# Left.net
KiCad netlist of a schematic drawn in EAGLE
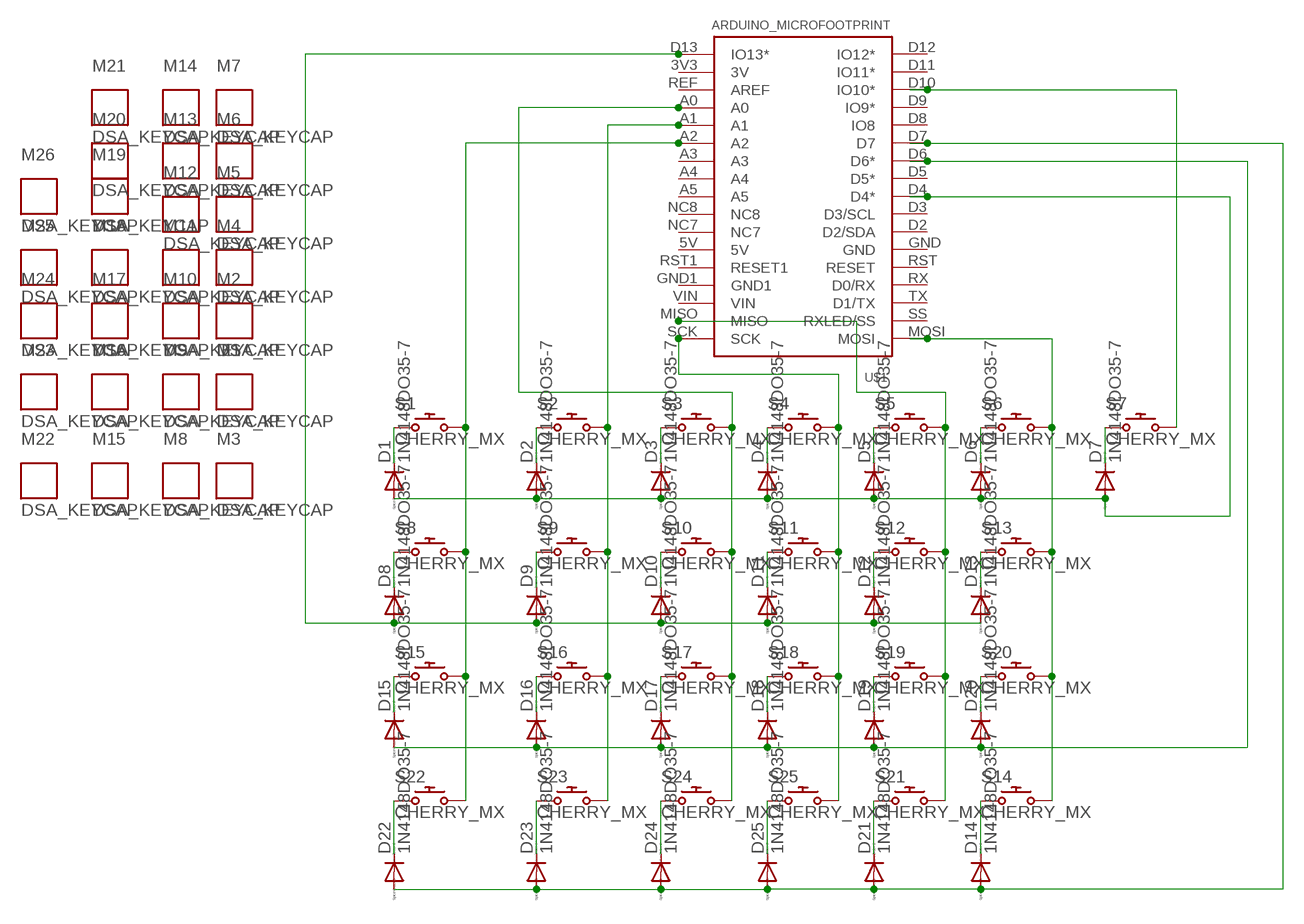
[diagram p0: schematic, sheet 1]

(export (version "E")
  (design (tool "Eeschema 10.0.6"))
  (components
    (comp (ref "D1")
      (value "1N4148DO35-7")
      (footprint "eagle-import:DO35-7")
      (libsource (lib "eagle-import") (part "1N4148DO35-7"))
    )
    (comp (ref "D2")
      (value "1N4148DO35-7")
      (footprint "eagle-import:DO35-7")
      (libsource (lib "eagle-import") (part "1N4148DO35-7"))
    )
    (comp (ref "D3")
      (value "1N4148DO35-7")
      (footprint "eagle-import:DO35-7")
      (libsource (lib "eagle-import") (part "1N4148DO35-7"))
    )
    (comp (ref "D4")
      (value "1N4148DO35-7")
      (footprint "eagle-import:DO35-7")
      (libsource (lib "eagle-import") (part "1N4148DO35-7"))
    )
    (comp (ref "D5")
      (value "1N4148DO35-7")
      (footprint "eagle-import:DO35-7")
      (libsource (lib "eagle-import") (part "1N4148DO35-7"))
    )
    (comp (ref "D6")
      (value "1N4148DO35-7")
      (footprint "eagle-import:DO35-7")
      (libsource (lib "eagle-import") (part "1N4148DO35-7"))
    )
    (comp (ref "D7")
      (value "1N4148DO35-7")
      (footprint "eagle-import:DO35-7")
      (libsource (lib "eagle-import") (part "1N4148DO35-7"))
    )
    (comp (ref "D8")
      (value "1N4148DO35-7")
      (footprint "eagle-import:DO35-7")
      (libsource (lib "eagle-import") (part "1N4148DO35-7"))
    )
    (comp (ref "D9")
      (value "1N4148DO35-7")
      (footprint "eagle-import:DO35-7")
      (libsource (lib "eagle-import") (part "1N4148DO35-7"))
    )
    (comp (ref "D10")
      (value "1N4148DO35-7")
      (footprint "eagle-import:DO35-7")
      (libsource (lib "eagle-import") (part "1N4148DO35-7"))
    )
    (comp (ref "D11")
      (value "1N4148DO35-7")
      (footprint "eagle-import:DO35-7")
      (libsource (lib "eagle-import") (part "1N4148DO35-7"))
    )
    (comp (ref "D12")
      (value "1N4148DO35-7")
      (footprint "eagle-import:DO35-7")
      (libsource (lib "eagle-import") (part "1N4148DO35-7"))
    )
    (comp (ref "D13")
      (value "1N4148DO35-7")
      (footprint "eagle-import:DO35-7")
      (libsource (lib "eagle-import") (part "1N4148DO35-7"))
    )
    (comp (ref "D14")
      (value "1N4148DO35-7")
      (footprint "eagle-import:DO35-7")
      (libsource (lib "eagle-import") (part "1N4148DO35-7"))
    )
    (comp (ref "D15")
      (value "1N4148DO35-7")
      (footprint "eagle-import:DO35-7")
      (libsource (lib "eagle-import") (part "1N4148DO35-7"))
    )
    (comp (ref "D16")
      (value "1N4148DO35-7")
      (footprint "eagle-import:DO35-7")
      (libsource (lib "eagle-import") (part "1N4148DO35-7"))
    )
    (comp (ref "D17")
      (value "1N4148DO35-7")
      (footprint "eagle-import:DO35-7")
      (libsource (lib "eagle-import") (part "1N4148DO35-7"))
    )
    (comp (ref "D18")
      (value "1N4148DO35-7")
      (footprint "eagle-import:DO35-7")
      (libsource (lib "eagle-import") (part "1N4148DO35-7"))
    )
    (comp (ref "D19")
      (value "1N4148DO35-7")
      (footprint "eagle-import:DO35-7")
      (libsource (lib "eagle-import") (part "1N4148DO35-7"))
    )
    (comp (ref "D20")
      (value "1N4148DO35-7")
      (footprint "eagle-import:DO35-7")
      (libsource (lib "eagle-import") (part "1N4148DO35-7"))
    )
    (comp (ref "D21")
      (value "1N4148DO35-7")
      (footprint "eagle-import:DO35-7")
      (libsource (lib "eagle-import") (part "1N4148DO35-7"))
    )
    (comp (ref "D22")
      (value "1N4148DO35-7")
      (footprint "eagle-import:DO35-7")
      (libsource (lib "eagle-import") (part "1N4148DO35-7"))
    )
    (comp (ref "D23")
      (value "1N4148DO35-7")
      (footprint "eagle-import:DO35-7")
      (libsource (lib "eagle-import") (part "1N4148DO35-7"))
    )
    (comp (ref "D24")
      (value "1N4148DO35-7")
      (footprint "eagle-import:DO35-7")
      (libsource (lib "eagle-import") (part "1N4148DO35-7"))
    )
    (comp (ref "D25")
      (value "1N4148DO35-7")
      (footprint "eagle-import:DO35-7")
      (libsource (lib "eagle-import") (part "1N4148DO35-7"))
    )
    (comp (ref "M1")
      (value "DSA_KEYCAP")
      (footprint "eagle-import:DSA_KEYCAP")
      (libsource (lib "eagle-import") (part "DSA_KEYCAP"))
    )
    (comp (ref "M2")
      (value "DSA_KEYCAP")
      (footprint "eagle-import:DSA_KEYCAP")
      (libsource (lib "eagle-import") (part "DSA_KEYCAP"))
    )
    (comp (ref "M3")
      (value "DSA_KEYCAP")
      (footprint "eagle-import:DSA_KEYCAP")
      (libsource (lib "eagle-import") (part "DSA_KEYCAP"))
    )
    (comp (ref "M4")
      (value "DSA_KEYCAP")
      (footprint "eagle-import:DSA_KEYCAP")
      (libsource (lib "eagle-import") (part "DSA_KEYCAP"))
    )
    (comp (ref "M5")
      (value "DSA_KEYCAP")
      (footprint "eagle-import:DSA_KEYCAP")
      (libsource (lib "eagle-import") (part "DSA_KEYCAP"))
    )
    (comp (ref "M6")
      (value "DSA_KEYCAP")
      (footprint "eagle-import:DSA_KEYCAP")
      (libsource (lib "eagle-import") (part "DSA_KEYCAP"))
    )
    (comp (ref "M7")
      (value "DSA_KEYCAP")
      (footprint "eagle-import:DSA_KEYCAP")
      (libsource (lib "eagle-import") (part "DSA_KEYCAP"))
    )
    (comp (ref "M8")
      (value "DSA_KEYCAP")
      (footprint "eagle-import:DSA_KEYCAP")
      (libsource (lib "eagle-import") (part "DSA_KEYCAP"))
    )
    (comp (ref "M9")
      (value "DSA_KEYCAP")
      (footprint "eagle-import:DSA_KEYCAP")
      (libsource (lib "eagle-import") (part "DSA_KEYCAP"))
    )
    (comp (ref "M10")
      (value "DSA_KEYCAP")
      (footprint "eagle-import:DSA_KEYCAP")
      (libsource (lib "eagle-import") (part "DSA_KEYCAP"))
    )
    (comp (ref "M11")
      (value "DSA_KEYCAP")
      (footprint "eagle-import:DSA_KEYCAP")
      (libsource (lib "eagle-import") (part "DSA_KEYCAP"))
    )
    (comp (ref "M12")
      (value "DSA_KEYCAP")
      (footprint "eagle-import:DSA_KEYCAP")
      (libsource (lib "eagle-import") (part "DSA_KEYCAP"))
    )
    (comp (ref "M13")
      (value "DSA_KEYCAP")
      (footprint "eagle-import:DSA_KEYCAP")
      (libsource (lib "eagle-import") (part "DSA_KEYCAP"))
    )
    (comp (ref "M14")
      (value "DSA_KEYCAP")
      (footprint "eagle-import:DSA_KEYCAP")
      (libsource (lib "eagle-import") (part "DSA_KEYCAP"))
    )
    (comp (ref "M15")
      (value "DSA_KEYCAP")
      (footprint "eagle-import:DSA_KEYCAP")
      (libsource (lib "eagle-import") (part "DSA_KEYCAP"))
    )
    (comp (ref "M16")
      (value "DSA_KEYCAP")
      (footprint "eagle-import:DSA_KEYCAP")
      (libsource (lib "eagle-import") (part "DSA_KEYCAP"))
    )
    (comp (ref "M17")
      (value "DSA_KEYCAP")
      (footprint "eagle-import:DSA_KEYCAP")
      (libsource (lib "eagle-import") (part "DSA_KEYCAP"))
    )
    (comp (ref "M18")
      (value "DSA_KEYCAP")
      (footprint "eagle-import:DSA_KEYCAP")
      (libsource (lib "eagle-import") (part "DSA_KEYCAP"))
    )
    (comp (ref "M19")
      (value "DSA_KEYCAP")
      (footprint "eagle-import:DSA_KEYCAP")
      (libsource (lib "eagle-import") (part "DSA_KEYCAP"))
    )
    (comp (ref "M20")
      (value "DSA_KEYCAP")
      (footprint "eagle-import:DSA_KEYCAP")
      (libsource (lib "eagle-import") (part "DSA_KEYCAP"))
    )
    (comp (ref "M21")
      (value "DSA_KEYCAP")
      (footprint "eagle-import:DSA_KEYCAP")
      (libsource (lib "eagle-import") (part "DSA_KEYCAP"))
    )
    (comp (ref "M22")
      (value "DSA_KEYCAP")
      (footprint "eagle-import:DSA_KEYCAP")
      (libsource (lib "eagle-import") (part "DSA_KEYCAP"))
    )
    (comp (ref "M23")
      (value "DSA_KEYCAP")
      (footprint "eagle-import:DSA_KEYCAP")
      (libsource (lib "eagle-import") (part "DSA_KEYCAP"))
    )
    (comp (ref "M24")
      (value "DSA_KEYCAP")
      (footprint "eagle-import:DSA_KEYCAP")
      (libsource (lib "eagle-import") (part "DSA_KEYCAP"))
    )
    (comp (ref "M25")
      (value "DSA_KEYCAP")
      (footprint "eagle-import:DSA_KEYCAP")
      (libsource (lib "eagle-import") (part "DSA_KEYCAP"))
    )
    (comp (ref "M26")
      (value "DSA_KEYCAP")
      (footprint "eagle-import:DSA_KEYCAP")
      (libsource (lib "eagle-import") (part "DSA_KEYCAP"))
    )
    (comp (ref "S1")
      (value "CHERRY_MX")
      (footprint "eagle-import:CHERRY_MX")
      (libsource (lib "eagle-import") (part "CHERRY_MX"))
    )
    (comp (ref "S2")
      (value "CHERRY_MX")
      (footprint "eagle-import:CHERRY_MX")
      (libsource (lib "eagle-import") (part "CHERRY_MX"))
    )
    (comp (ref "S3")
      (value "CHERRY_MX")
      (footprint "eagle-import:CHERRY_MX")
      (libsource (lib "eagle-import") (part "CHERRY_MX"))
    )
    (comp (ref "S4")
      (value "CHERRY_MX")
      (footprint "eagle-import:CHERRY_MX")
      (libsource (lib "eagle-import") (part "CHERRY_MX"))
    )
    (comp (ref "S5")
      (value "CHERRY_MX")
      (footprint "eagle-import:CHERRY_MX")
      (libsource (lib "eagle-import") (part "CHERRY_MX"))
    )
    (comp (ref "S6")
      (value "CHERRY_MX")
      (footprint "eagle-import:CHERRY_MX")
      (libsource (lib "eagle-import") (part "CHERRY_MX"))
    )
    (comp (ref "S7")
      (value "CHERRY_MX")
      (footprint "eagle-import:CHERRY_MX")
      (libsource (lib "eagle-import") (part "CHERRY_MX"))
    )
    (comp (ref "S8")
      (value "CHERRY_MX")
      (footprint "eagle-import:CHERRY_MX")
      (libsource (lib "eagle-import") (part "CHERRY_MX"))
    )
    (comp (ref "S9")
      (value "CHERRY_MX")
      (footprint "eagle-import:CHERRY_MX")
      (libsource (lib "eagle-import") (part "CHERRY_MX"))
    )
    (comp (ref "S10")
      (value "CHERRY_MX")
      (footprint "eagle-import:CHERRY_MX")
      (libsource (lib "eagle-import") (part "CHERRY_MX"))
    )
    (comp (ref "S11")
      (value "CHERRY_MX")
      (footprint "eagle-import:CHERRY_MX")
      (libsource (lib "eagle-import") (part "CHERRY_MX"))
    )
    (comp (ref "S12")
      (value "CHERRY_MX")
      (footprint "eagle-import:CHERRY_MX")
      (libsource (lib "eagle-import") (part "CHERRY_MX"))
    )
    (comp (ref "S13")
      (value "CHERRY_MX")
      (footprint "eagle-import:CHERRY_MX")
      (libsource (lib "eagle-import") (part "CHERRY_MX"))
    )
    (comp (ref "S14")
      (value "CHERRY_MX")
      (footprint "eagle-import:CHERRY_MX")
      (libsource (lib "eagle-import") (part "CHERRY_MX"))
    )
    (comp (ref "S15")
      (value "CHERRY_MX")
      (footprint "eagle-import:CHERRY_MX")
      (libsource (lib "eagle-import") (part "CHERRY_MX"))
    )
    (comp (ref "S16")
      (value "CHERRY_MX")
      (footprint "eagle-import:CHERRY_MX")
      (libsource (lib "eagle-import") (part "CHERRY_MX"))
    )
    (comp (ref "S17")
      (value "CHERRY_MX")
      (footprint "eagle-import:CHERRY_MX")
      (libsource (lib "eagle-import") (part "CHERRY_MX"))
    )
    (comp (ref "S18")
      (value "CHERRY_MX")
      (footprint "eagle-import:CHERRY_MX")
      (libsource (lib "eagle-import") (part "CHERRY_MX"))
    )
    (comp (ref "S19")
      (value "CHERRY_MX")
      (footprint "eagle-import:CHERRY_MX")
      (libsource (lib "eagle-import") (part "CHERRY_MX"))
    )
    (comp (ref "S20")
      (value "CHERRY_MX")
      (footprint "eagle-import:CHERRY_MX")
      (libsource (lib "eagle-import") (part "CHERRY_MX"))
    )
    (comp (ref "S21")
      (value "CHERRY_MX")
      (footprint "eagle-import:CHERRY_MX")
      (libsource (lib "eagle-import") (part "CHERRY_MX"))
    )
    (comp (ref "S22")
      (value "CHERRY_MX")
      (footprint "eagle-import:CHERRY_MX")
      (libsource (lib "eagle-import") (part "CHERRY_MX"))
    )
    (comp (ref "S23")
      (value "CHERRY_MX")
      (footprint "eagle-import:CHERRY_MX")
      (libsource (lib "eagle-import") (part "CHERRY_MX"))
    )
    (comp (ref "S24")
      (value "CHERRY_MX")
      (footprint "eagle-import:CHERRY_MX")
      (libsource (lib "eagle-import") (part "CHERRY_MX"))
    )
    (comp (ref "S25")
      (value "CHERRY_MX")
      (footprint "eagle-import:CHERRY_MX")
      (libsource (lib "eagle-import") (part "CHERRY_MX"))
    )
    (comp (ref "U$1")
      (value "ARDUINO_MICROFOOTPRINT")
      (footprint "eagle-import:ARDUINO-MICRO")
      (libsource (lib "eagle-import") (part "ARDUINO_MICROFOOTPRINT"))
    )
  )
  (nets
    (net (code "1") (name "Net-(D14-PadA)") (class "Default")
      (node (ref "D14") (pin "A") (pinfunction "A_A") (pintype "passive"))
      (node (ref "D21") (pin "A") (pinfunction "A_A") (pintype "passive"))
      (node (ref "D22") (pin "A") (pinfunction "A_A") (pintype "passive"))
      (node (ref "D23") (pin "A") (pinfunction "A_A") (pintype "passive"))
      (node (ref "D24") (pin "A") (pinfunction "A_A") (pintype "passive"))
      (node (ref "D25") (pin "A") (pinfunction "A_A") (pintype "passive"))
      (node (ref "U$1") (pin "D7") (pinfunction "D7_D7") (pintype "bidirectional"))
    )
    (net (code "2") (name "Net-(S1-1)") (class "Default")
      (node (ref "D1") (pin "C") (pinfunction "C_C") (pintype "passive"))
      (node (ref "S1") (pin "S1") (pinfunction "1_S1") (pintype "passive"))
    )
    (net (code "3") (name "Net-(S1-2)") (class "Default")
      (node (ref "S1") (pin "S2") (pinfunction "2_S2") (pintype "passive"))
      (node (ref "S15") (pin "S2") (pinfunction "2_S2") (pintype "passive"))
      (node (ref "S22") (pin "S2") (pinfunction "2_S2") (pintype "passive"))
      (node (ref "S8") (pin "S2") (pinfunction "2_S2") (pintype "passive"))
      (node (ref "U$1") (pin "A2") (pinfunction "A2_A2") (pintype "bidirectional"))
    )
    (net (code "4") (name "Net-(S2-1)") (class "Default")
      (node (ref "D2") (pin "C") (pinfunction "C_C") (pintype "passive"))
      (node (ref "S2") (pin "S1") (pinfunction "1_S1") (pintype "passive"))
    )
    (net (code "5") (name "Net-(S3-1)") (class "Default")
      (node (ref "D3") (pin "C") (pinfunction "C_C") (pintype "passive"))
      (node (ref "S3") (pin "S1") (pinfunction "1_S1") (pintype "passive"))
    )
    (net (code "6") (name "Net-(S4-1)") (class "Default")
      (node (ref "D4") (pin "C") (pinfunction "C_C") (pintype "passive"))
      (node (ref "S4") (pin "S1") (pinfunction "1_S1") (pintype "passive"))
    )
    (net (code "7") (name "Net-(S5-1)") (class "Default")
      (node (ref "D5") (pin "C") (pinfunction "C_C") (pintype "passive"))
      (node (ref "S5") (pin "S1") (pinfunction "1_S1") (pintype "passive"))
    )
    (net (code "8") (name "Net-(S6-1)") (class "Default")
      (node (ref "D6") (pin "C") (pinfunction "C_C") (pintype "passive"))
      (node (ref "S6") (pin "S1") (pinfunction "1_S1") (pintype "passive"))
    )
    (net (code "9") (name "Net-(S7-1)") (class "Default")
      (node (ref "D7") (pin "C") (pinfunction "C_C") (pintype "passive"))
      (node (ref "S7") (pin "S1") (pinfunction "1_S1") (pintype "passive"))
    )
    (net (code "10") (name "Net-(S7-2)") (class "Default")
      (node (ref "S7") (pin "S2") (pinfunction "2_S2") (pintype "passive"))
      (node (ref "U$1") (pin "D10") (pinfunction "IO10*_D10") (pintype "bidirectional"))
    )
    (net (code "11") (name "Net-(S8-1)") (class "Default")
      (node (ref "D8") (pin "C") (pinfunction "C_C") (pintype "passive"))
      (node (ref "S8") (pin "S1") (pinfunction "1_S1") (pintype "passive"))
    )
    (net (code "12") (name "Net-(S9-1)") (class "Default")
      (node (ref "D9") (pin "C") (pinfunction "C_C") (pintype "passive"))
      (node (ref "S9") (pin "S1") (pinfunction "1_S1") (pintype "passive"))
    )
    (net (code "13") (name "Net-(S10-1)") (class "Default")
      (node (ref "D10") (pin "C") (pinfunction "C_C") (pintype "passive"))
      (node (ref "S10") (pin "S1") (pinfunction "1_S1") (pintype "passive"))
    )
    (net (code "14") (name "Net-(S10-2)") (class "Default")
      (node (ref "S10") (pin "S2") (pinfunction "2_S2") (pintype "passive"))
      (node (ref "S17") (pin "S2") (pinfunction "2_S2") (pintype "passive"))
      (node (ref "S24") (pin "S2") (pinfunction "2_S2") (pintype "passive"))
      (node (ref "S3") (pin "S2") (pinfunction "2_S2") (pintype "passive"))
      (node (ref "U$1") (pin "A0") (pinfunction "A0_A0") (pintype "bidirectional"))
    )
    (net (code "15") (name "Net-(S11-1)") (class "Default")
      (node (ref "D11") (pin "C") (pinfunction "C_C") (pintype "passive"))
      (node (ref "S11") (pin "S1") (pinfunction "1_S1") (pintype "passive"))
    )
    (net (code "16") (name "Net-(S11-2)") (class "Default")
      (node (ref "S11") (pin "S2") (pinfunction "2_S2") (pintype "passive"))
      (node (ref "S18") (pin "S2") (pinfunction "2_S2") (pintype "passive"))
      (node (ref "S25") (pin "S2") (pinfunction "2_S2") (pintype "passive"))
      (node (ref "S4") (pin "S2") (pinfunction "2_S2") (pintype "passive"))
      (node (ref "U$1") (pin "SCK") (pinfunction "SCK_SCK") (pintype "bidirectional"))
    )
    (net (code "17") (name "Net-(S12-1)") (class "Default")
      (node (ref "D12") (pin "C") (pinfunction "C_C") (pintype "passive"))
      (node (ref "S12") (pin "S1") (pinfunction "1_S1") (pintype "passive"))
    )
    (net (code "18") (name "Net-(S12-2)") (class "Default")
      (node (ref "S12") (pin "S2") (pinfunction "2_S2") (pintype "passive"))
      (node (ref "S19") (pin "S2") (pinfunction "2_S2") (pintype "passive"))
      (node (ref "S21") (pin "S2") (pinfunction "2_S2") (pintype "passive"))
      (node (ref "S5") (pin "S2") (pinfunction "2_S2") (pintype "passive"))
      (node (ref "U$1") (pin "MISO") (pinfunction "MISO_MISO") (pintype "bidirectional"))
    )
    (net (code "19") (name "Net-(S13-1)") (class "Default")
      (node (ref "D13") (pin "C") (pinfunction "C_C") (pintype "passive"))
      (node (ref "S13") (pin "S1") (pinfunction "1_S1") (pintype "passive"))
    )
    (net (code "20") (name "Net-(S13-2)") (class "Default")
      (node (ref "S13") (pin "S2") (pinfunction "2_S2") (pintype "passive"))
      (node (ref "S14") (pin "S2") (pinfunction "2_S2") (pintype "passive"))
      (node (ref "S20") (pin "S2") (pinfunction "2_S2") (pintype "passive"))
      (node (ref "S6") (pin "S2") (pinfunction "2_S2") (pintype "passive"))
      (node (ref "U$1") (pin "MOSI") (pinfunction "MOSI_MOSI") (pintype "bidirectional"))
    )
    (net (code "21") (name "Net-(S14-1)") (class "Default")
      (node (ref "D14") (pin "C") (pinfunction "C_C") (pintype "passive"))
      (node (ref "S14") (pin "S1") (pinfunction "1_S1") (pintype "passive"))
    )
    (net (code "22") (name "Net-(S15-1)") (class "Default")
      (node (ref "D15") (pin "C") (pinfunction "C_C") (pintype "passive"))
      (node (ref "S15") (pin "S1") (pinfunction "1_S1") (pintype "passive"))
    )
    (net (code "23") (name "Net-(S16-1)") (class "Default")
      (node (ref "D16") (pin "C") (pinfunction "C_C") (pintype "passive"))
      (node (ref "S16") (pin "S1") (pinfunction "1_S1") (pintype "passive"))
    )
    (net (code "24") (name "Net-(S16-2)") (class "Default")
      (node (ref "S16") (pin "S2") (pinfunction "2_S2") (pintype "passive"))
      (node (ref "S2") (pin "S2") (pinfunction "2_S2") (pintype "passive"))
      (node (ref "S23") (pin "S2") (pinfunction "2_S2") (pintype "passive"))
      (node (ref "S9") (pin "S2") (pinfunction "2_S2") (pintype "passive"))
      (node (ref "U$1") (pin "A1") (pinfunction "A1_A1") (pintype "bidirectional"))
    )
    (net (code "25") (name "Net-(S17-1)") (class "Default")
      (node (ref "D17") (pin "C") (pinfunction "C_C") (pintype "passive"))
      (node (ref "S17") (pin "S1") (pinfunction "1_S1") (pintype "passive"))
    )
    (net (code "26") (name "Net-(S18-1)") (class "Default")
      (node (ref "D18") (pin "C") (pinfunction "C_C") (pintype "passive"))
      (node (ref "S18") (pin "S1") (pinfunction "1_S1") (pintype "passive"))
    )
    (net (code "27") (name "Net-(S19-1)") (class "Default")
      (node (ref "D19") (pin "C") (pinfunction "C_C") (pintype "passive"))
      (node (ref "S19") (pin "S1") (pinfunction "1_S1") (pintype "passive"))
    )
    (net (code "28") (name "Net-(S20-1)") (class "Default")
      (node (ref "D20") (pin "C") (pinfunction "C_C") (pintype "passive"))
      (node (ref "S20") (pin "S1") (pinfunction "1_S1") (pintype "passive"))
    )
    (net (code "29") (name "Net-(S21-1)") (class "Default")
      (node (ref "D21") (pin "C") (pinfunction "C_C") (pintype "passive"))
      (node (ref "S21") (pin "S1") (pinfunction "1_S1") (pintype "passive"))
    )
    (net (code "30") (name "Net-(S22-1)") (class "Default")
      (node (ref "D22") (pin "C") (pinfunction "C_C") (pintype "passive"))
      (node (ref "S22") (pin "S1") (pinfunction "1_S1") (pintype "passive"))
    )
    (net (code "31") (name "Net-(S23-1)") (class "Default")
      (node (ref "D23") (pin "C") (pinfunction "C_C") (pintype "passive"))
      (node (ref "S23") (pin "S1") (pinfunction "1_S1") (pintype "passive"))
    )
    (net (code "32") (name "Net-(S24-1)") (class "Default")
      (node (ref "D24") (pin "C") (pinfunction "C_C") (pintype "passive"))
      (node (ref "S24") (pin "S1") (pinfunction "1_S1") (pintype "passive"))
    )
    (net (code "33") (name "Net-(S25-1)") (class "Default")
      (node (ref "D25") (pin "C") (pinfunction "C_C") (pintype "passive"))
      (node (ref "S25") (pin "S1") (pinfunction "1_S1") (pintype "passive"))
    )
    (net (code "34") (name "Net-(U$1-D4*)") (class "Default")
      (node (ref "D1") (pin "A") (pinfunction "A_A") (pintype "passive"))
      (node (ref "D2") (pin "A") (pinfunction "A_A") (pintype "passive"))
      (node (ref "D3") (pin "A") (pinfunction "A_A") (pintype "passive"))
      (node (ref "D4") (pin "A") (pinfunction "A_A") (pintype "passive"))
      (node (ref "D5") (pin "A") (pinfunction "A_A") (pintype "passive"))
      (node (ref "D6") (pin "A") (pinfunction "A_A") (pintype "passive"))
      (node (ref "D7") (pin "A") (pinfunction "A_A") (pintype "passive"))
      (node (ref "U$1") (pin "D4") (pinfunction "D4*_D4") (pintype "bidirectional"))
    )
    (net (code "35") (name "Net-(U$1-D6*)") (class "Default")
      (node (ref "D15") (pin "A") (pinfunction "A_A") (pintype "passive"))
      (node (ref "D16") (pin "A") (pinfunction "A_A") (pintype "passive"))
      (node (ref "D17") (pin "A") (pinfunction "A_A") (pintype "passive"))
      (node (ref "D18") (pin "A") (pinfunction "A_A") (pintype "passive"))
      (node (ref "D19") (pin "A") (pinfunction "A_A") (pintype "passive"))
      (node (ref "D20") (pin "A") (pinfunction "A_A") (pintype "passive"))
      (node (ref "U$1") (pin "D6") (pinfunction "D6*_D6") (pintype "bidirectional"))
    )
    (net (code "36") (name "Net-(U$1-IO13*)") (class "Default")
      (node (ref "D10") (pin "A") (pinfunction "A_A") (pintype "passive"))
      (node (ref "D11") (pin "A") (pinfunction "A_A") (pintype "passive"))
      (node (ref "D12") (pin "A") (pinfunction "A_A") (pintype "passive"))
      (node (ref "D13") (pin "A") (pinfunction "A_A") (pintype "passive"))
      (node (ref "D8") (pin "A") (pinfunction "A_A") (pintype "passive"))
      (node (ref "D9") (pin "A") (pinfunction "A_A") (pintype "passive"))
      (node (ref "U$1") (pin "D13") (pinfunction "IO13*_D13") (pintype "bidirectional"))
    )
    (net (code "37") (name "unconnected-(U$1-3V-Pad3V3)") (class "Default")
      (node (ref "U$1") (pin "3V3") (pinfunction "3V_3V3") (pintype "bidirectional"))
    )
    (net (code "38") (name "unconnected-(U$1-AREF-PadREF)") (class "Default")
      (node (ref "U$1") (pin "REF") (pinfunction "AREF_REF") (pintype "bidirectional"))
    )
    (net (code "39") (name "unconnected-(U$1-D0{slash}RX-PadRX)") (class "Default")
      (node (ref "U$1") (pin "RX") (pinfunction "D0/RX_RX") (pintype "bidirectional"))
    )
    (net (code "40") (name "unconnected-(U$1-D1{slash}TX-PadTX)") (class "Default")
      (node (ref "U$1") (pin "TX") (pinfunction "D1/TX_TX") (pintype "bidirectional"))
    )
    (net (code "41") (name "unconnected-(U$1-D2{slash}SDA-PadD2)") (class "Default")
      (node (ref "U$1") (pin "D2") (pinfunction "D2/SDA_D2") (pintype "bidirectional"))
    )
    (net (code "42") (name "unconnected-(U$1-D3{slash}SCL-PadD3)") (class "Default")
      (node (ref "U$1") (pin "D3") (pinfunction "D3/SCL_D3") (pintype "bidirectional"))
    )
    (net (code "43") (name "unconnected-(U$1-D5*-PadD5)") (class "Default")
      (node (ref "U$1") (pin "D5") (pinfunction "D5*_D5") (pintype "bidirectional"))
    )
    (net (code "44") (name "unconnected-(U$1-IO8-PadD8)") (class "Default")
      (node (ref "U$1") (pin "D8") (pinfunction "IO8_D8") (pintype "bidirectional"))
    )
    (net (code "45") (name "unconnected-(U$1-IO9*-PadD9)") (class "Default")
      (node (ref "U$1") (pin "D9") (pinfunction "IO9*_D9") (pintype "bidirectional"))
    )
    (net (code "46") (name "unconnected-(U$1-IO11*-PadD11)") (class "Default")
      (node (ref "U$1") (pin "D11") (pinfunction "IO11*_D11") (pintype "bidirectional"))
    )
    (net (code "47") (name "unconnected-(U$1-IO12*-PadD12)") (class "Default")
      (node (ref "U$1") (pin "D12") (pinfunction "IO12*_D12") (pintype "bidirectional"))
    )
    (net (code "48") (name "unconnected-(U$1-Pad5V)") (class "Default")
      (node (ref "U$1") (pin "5V") (pinfunction "5V_5V") (pintype "bidirectional"))
    )
    (net (code "49") (name "unconnected-(U$1-PadA3)") (class "Default")
      (node (ref "U$1") (pin "A3") (pinfunction "A3_A3") (pintype "bidirectional"))
    )
    (net (code "50") (name "unconnected-(U$1-PadA4)") (class "Default")
      (node (ref "U$1") (pin "A4") (pinfunction "A4_A4") (pintype "bidirectional"))
    )
    (net (code "51") (name "unconnected-(U$1-PadA5)") (class "Default")
      (node (ref "U$1") (pin "A5") (pinfunction "A5_A5") (pintype "bidirectional"))
    )
    (net (code "52") (name "unconnected-(U$1-PadGND)") (class "Default")
      (node (ref "U$1") (pin "GND") (pinfunction "GND_GND") (pintype "bidirectional"))
    )
    (net (code "53") (name "unconnected-(U$1-PadGND1)") (class "Default")
      (node (ref "U$1") (pin "GND1") (pinfunction "GND1_GND1") (pintype "bidirectional"))
    )
    (net (code "54") (name "unconnected-(U$1-PadNC7)") (class "Default")
      (node (ref "U$1") (pin "NC7") (pinfunction "NC7_NC7") (pintype "bidirectional"))
    )
    (net (code "55") (name "unconnected-(U$1-PadNC8)") (class "Default")
      (node (ref "U$1") (pin "NC8") (pinfunction "NC8_NC8") (pintype "bidirectional"))
    )
    (net (code "56") (name "unconnected-(U$1-PadVIN)") (class "Default")
      (node (ref "U$1") (pin "VIN") (pinfunction "VIN_VIN") (pintype "bidirectional"))
    )
    (net (code "57") (name "unconnected-(U$1-RESET-PadRST)") (class "Default")
      (node (ref "U$1") (pin "RST") (pinfunction "RESET_RST") (pintype "bidirectional"))
    )
    (net (code "58") (name "unconnected-(U$1-RESET1-PadRST1)") (class "Default")
      (node (ref "U$1") (pin "RST1") (pinfunction "RESET1_RST1") (pintype "bidirectional"))
    )
    (net (code "59") (name "unconnected-(U$1-RXLED{slash}SS-PadSS)") (class "Default")
      (node (ref "U$1") (pin "SS") (pinfunction "RXLED/SS_SS") (pintype "bidirectional"))
    )
  )
)
